# controllerM2.net
KiCad netlist of a schematic drawn in EAGLE
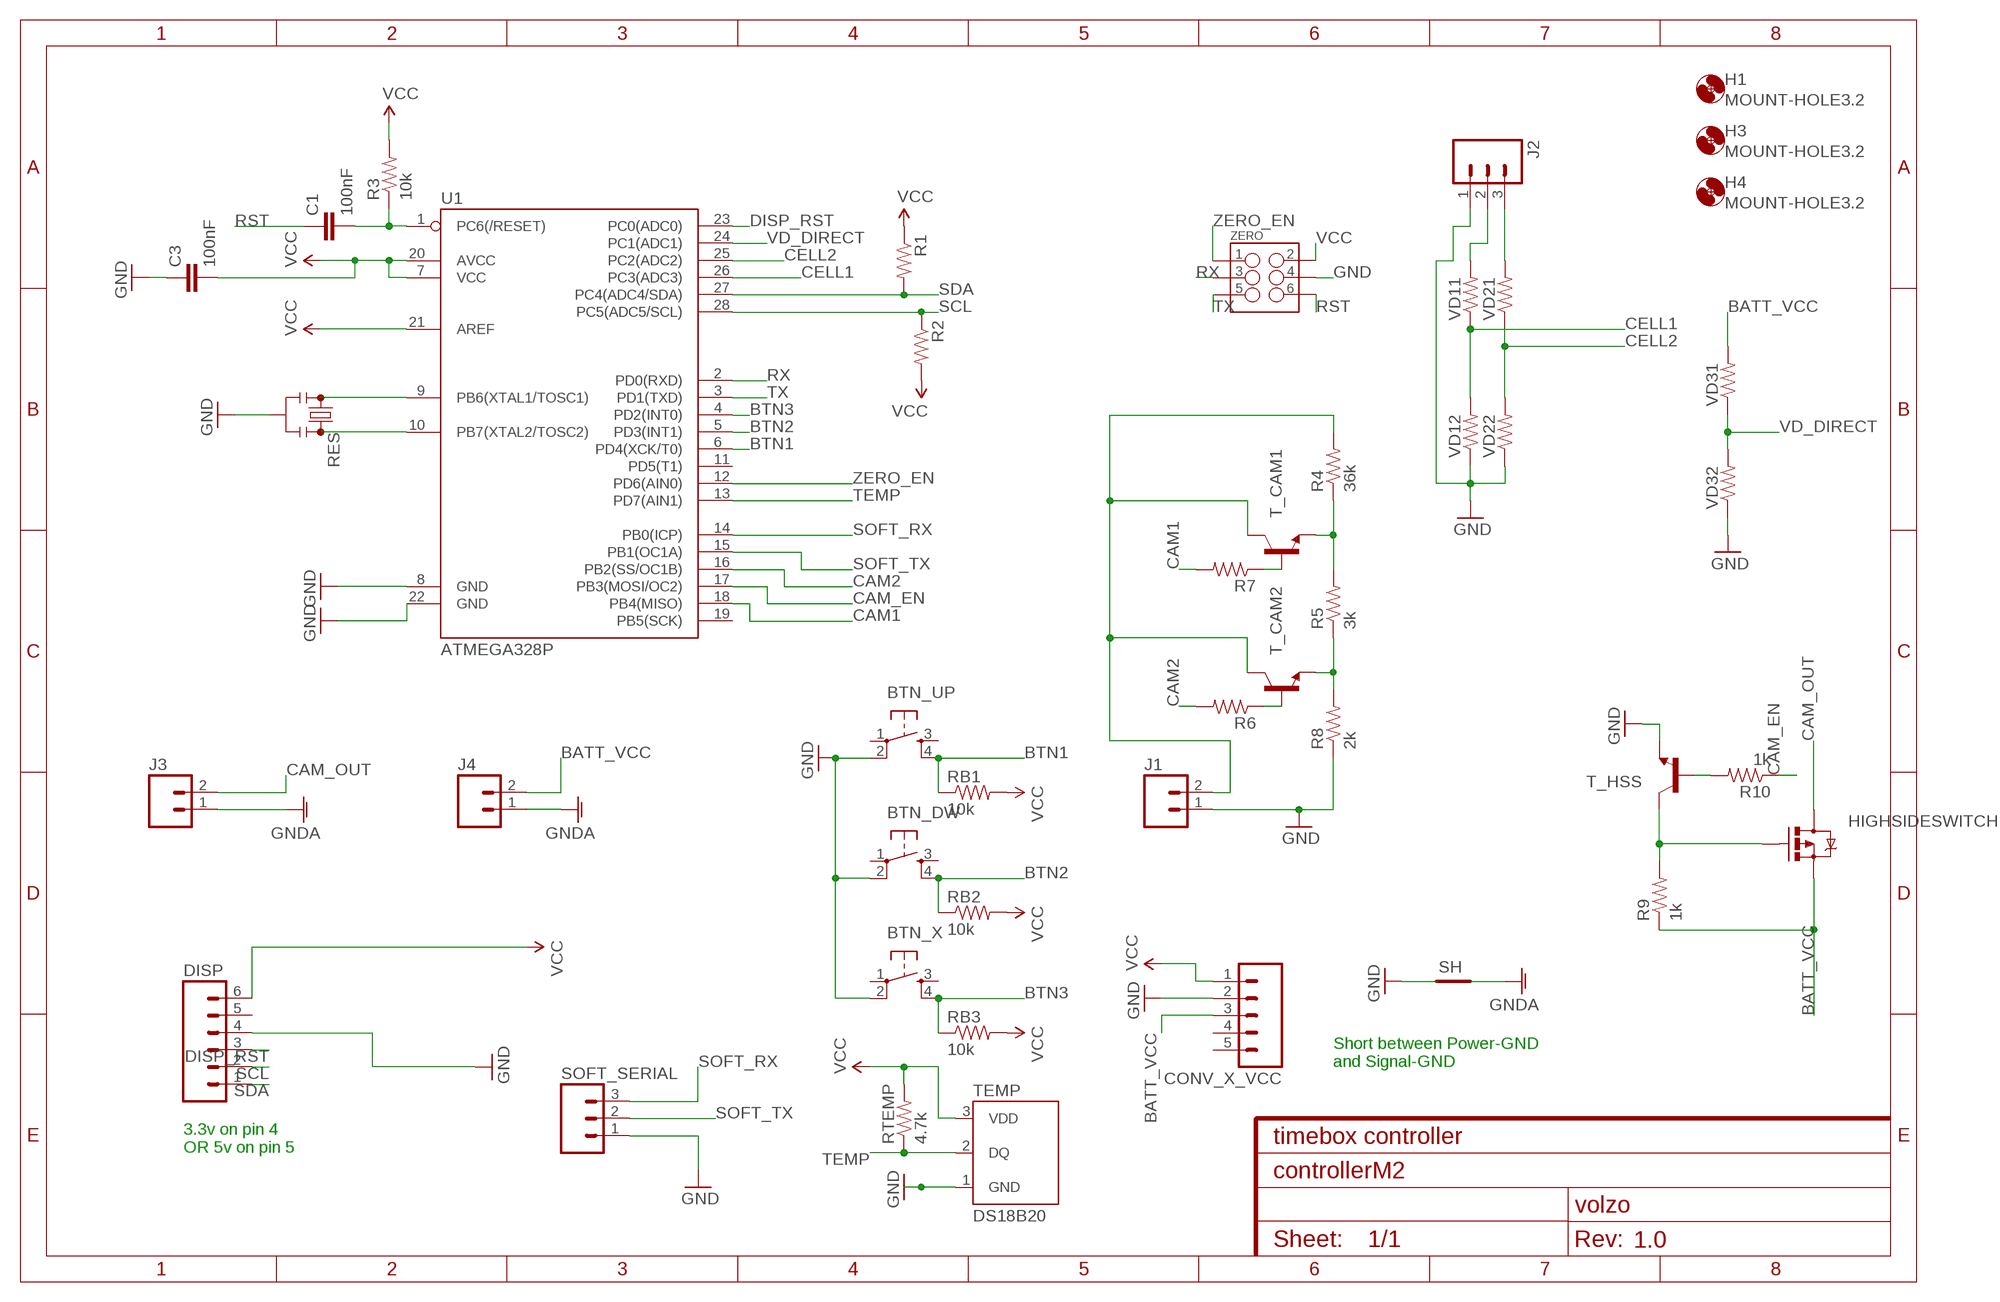
[diagram p0: schematic, sheet 1]

(export (version "E")
  (design (tool "Eeschema 10.0.6"))
  (components
    (comp (ref "BTN_DW")
      (value "TAC_SWITCHPTH")
      (footprint "eagle-import:TACTILE-PTH")
      (libsource (lib "eagle-import") (part "TAC_SWITCHPTH"))
    )
    (comp (ref "BTN_UP")
      (value "TAC_SWITCHPTH")
      (footprint "eagle-import:TACTILE-PTH")
      (libsource (lib "eagle-import") (part "TAC_SWITCHPTH"))
    )
    (comp (ref "BTN_X")
      (value "TAC_SWITCHPTH")
      (footprint "eagle-import:TACTILE-PTH")
      (libsource (lib "eagle-import") (part "TAC_SWITCHPTH"))
    )
    (comp (ref "C1")
      (value "100nF")
      (footprint "eagle-import:CAP-PTH-SMALL")
      (libsource (lib "eagle-import") (part "CAPPTH"))
    )
    (comp (ref "C3")
      (value "100nF")
      (footprint "eagle-import:CAP-PTH-SMALL")
      (libsource (lib "eagle-import") (part "CAPPTH"))
    )
    (comp (ref "CONV_X_VCC")
      (value "M05LOCK")
      (footprint "eagle-import:1X05_LOCK")
      (libsource (lib "eagle-import") (part "M05LOCK"))
    )
    (comp (ref "DISP")
      (value "M06FEMALE_LOCK")
      (footprint "eagle-import:1X06_FEMALE_LOCK.010")
      (libsource (lib "eagle-import") (part "M06FEMALE_LOCK"))
    )
    (comp (ref "H1")
      (value "MOUNT-HOLE3.2")
      (footprint "eagle-import:3,2")
      (libsource (lib "eagle-import") (part "MOUNT-HOLE3.2"))
    )
    (comp (ref "H3")
      (value "MOUNT-HOLE3.2")
      (footprint "eagle-import:3,2")
      (libsource (lib "eagle-import") (part "MOUNT-HOLE3.2"))
    )
    (comp (ref "H4")
      (value "MOUNT-HOLE3.2")
      (footprint "eagle-import:3,2")
      (libsource (lib "eagle-import") (part "MOUNT-HOLE3.2"))
    )
    (comp (ref "HIGHSIDESWITCH")
      (value "MOSFET-PCHANNELNDP6020P_20V_24A_LOW_VGS_TH")
      (footprint "eagle-import:TO220V")
      (libsource (lib "eagle-import") (part "MOSFET-PCHANNELNDP6020P_20V_24A_LOW_VGS_TH"))
    )
    (comp (ref "J1")
      (value "M02LOCK")
      (footprint "eagle-import:1X02_LOCK")
      (libsource (lib "eagle-import") (part "M02LOCK"))
    )
    (comp (ref "J2")
      (value "M03LOCK")
      (footprint "eagle-import:1X03_LOCK")
      (libsource (lib "eagle-import") (part "M03LOCK"))
    )
    (comp (ref "J3")
      (value "M023.5MM_LOCK")
      (footprint "eagle-import:SCREWTERMINAL-3.5MM-2_LOCK")
      (libsource (lib "eagle-import") (part "M023.5MM_LOCK"))
    )
    (comp (ref "J4")
      (value "M023.5MM_LOCK")
      (footprint "eagle-import:SCREWTERMINAL-3.5MM-2_LOCK")
      (libsource (lib "eagle-import") (part "M023.5MM_LOCK"))
    )
    (comp (ref "R1")
      (value "RESISTORAXIAL-0.3")
      (footprint "eagle-import:AXIAL-0.3")
      (libsource (lib "eagle-import") (part "RESISTORAXIAL-0.3"))
    )
    (comp (ref "R2")
      (value "RESISTORAXIAL-0.3")
      (footprint "eagle-import:AXIAL-0.3")
      (libsource (lib "eagle-import") (part "RESISTORAXIAL-0.3"))
    )
    (comp (ref "R3")
      (value "10k")
      (footprint "eagle-import:AXIAL-0.3")
      (libsource (lib "eagle-import") (part "RESISTORAXIAL-0.3"))
    )
    (comp (ref "R4")
      (value "36k")
      (footprint "eagle-import:AXIAL-0.3")
      (libsource (lib "eagle-import") (part "RESISTORAXIAL-0.3"))
    )
    (comp (ref "R5")
      (value "3k")
      (footprint "eagle-import:AXIAL-0.3")
      (libsource (lib "eagle-import") (part "RESISTORAXIAL-0.3"))
    )
    (comp (ref "R6")
      (value "RESISTORAXIAL-0.3")
      (footprint "eagle-import:AXIAL-0.3")
      (libsource (lib "eagle-import") (part "RESISTORAXIAL-0.3"))
    )
    (comp (ref "R7")
      (value "RESISTORAXIAL-0.3")
      (footprint "eagle-import:AXIAL-0.3")
      (libsource (lib "eagle-import") (part "RESISTORAXIAL-0.3"))
    )
    (comp (ref "R8")
      (value "2k")
      (footprint "eagle-import:AXIAL-0.3")
      (libsource (lib "eagle-import") (part "RESISTORAXIAL-0.3"))
    )
    (comp (ref "R9")
      (value "1k")
      (footprint "eagle-import:AXIAL-0.3")
      (libsource (lib "eagle-import") (part "RESISTORAXIAL-0.3"))
    )
    (comp (ref "R10")
      (value "1k")
      (footprint "eagle-import:AXIAL-0.3")
      (libsource (lib "eagle-import") (part "RESISTORAXIAL-0.3"))
    )
    (comp (ref "RB1")
      (value "10k")
      (footprint "eagle-import:AXIAL-0.3")
      (libsource (lib "eagle-import") (part "RESISTORAXIAL-0.3"))
    )
    (comp (ref "RB2")
      (value "10k")
      (footprint "eagle-import:AXIAL-0.3")
      (libsource (lib "eagle-import") (part "RESISTORAXIAL-0.3"))
    )
    (comp (ref "RB3")
      (value "10k")
      (footprint "eagle-import:AXIAL-0.3")
      (libsource (lib "eagle-import") (part "RESISTORAXIAL-0.3"))
    )
    (comp (ref "RES")
      (value "RESONATORPTH")
      (footprint "eagle-import:RESONATOR-PTH")
      (libsource (lib "eagle-import") (part "RESONATORPTH"))
    )
    (comp (ref "RTEMP")
      (value "4.7k")
      (footprint "eagle-import:AXIAL-0.3")
      (libsource (lib "eagle-import") (part "RESISTORAXIAL-0.3"))
    )
    (comp (ref "SH")
      (value "SHORT-HT5")
      (footprint "eagle-import:SHORT_TOP-50")
      (libsource (lib "eagle-import") (part "SHORT-HT5"))
    )
    (comp (ref "SOFT_SERIAL")
      (value "M03LOCK")
      (footprint "eagle-import:1X03_LOCK")
      (libsource (lib "eagle-import") (part "M03LOCK"))
    )
    (comp (ref "TEMP")
      (value "DS18B20")
      (footprint "eagle-import:TO-92-AMMO")
      (libsource (lib "eagle-import") (part "DS18B20"))
    )
    (comp (ref "T_CAM1")
      (value "TRANSISTOR_NPN2N3904")
      (footprint "eagle-import:TO-92")
      (libsource (lib "eagle-import") (part "TRANSISTOR_NPN2N3904"))
    )
    (comp (ref "T_CAM2")
      (value "TRANSISTOR_NPN2N3904")
      (footprint "eagle-import:TO-92")
      (libsource (lib "eagle-import") (part "TRANSISTOR_NPN2N3904"))
    )
    (comp (ref "T_HSS")
      (value "TRANSISTOR_NPN2N3904")
      (footprint "eagle-import:TO-92")
      (libsource (lib "eagle-import") (part "TRANSISTOR_NPN2N3904"))
    )
    (comp (ref "U1")
      (value "ATMEGA328P")
      (footprint "eagle-import:DIL28-3")
      (libsource (lib "eagle-import") (part "ATMEGA328P_PDIP"))
    )
    (comp (ref "VD11")
      (value "RESISTORAXIAL-0.3")
      (footprint "eagle-import:AXIAL-0.3")
      (libsource (lib "eagle-import") (part "RESISTORAXIAL-0.3"))
    )
    (comp (ref "VD12")
      (value "RESISTORAXIAL-0.3")
      (footprint "eagle-import:AXIAL-0.3")
      (libsource (lib "eagle-import") (part "RESISTORAXIAL-0.3"))
    )
    (comp (ref "VD21")
      (value "RESISTORAXIAL-0.3")
      (footprint "eagle-import:AXIAL-0.3")
      (libsource (lib "eagle-import") (part "RESISTORAXIAL-0.3"))
    )
    (comp (ref "VD22")
      (value "RESISTORAXIAL-0.3")
      (footprint "eagle-import:AXIAL-0.3")
      (libsource (lib "eagle-import") (part "RESISTORAXIAL-0.3"))
    )
    (comp (ref "VD31")
      (value "RESISTORAXIAL-0.3")
      (footprint "eagle-import:AXIAL-0.3")
      (libsource (lib "eagle-import") (part "RESISTORAXIAL-0.3"))
    )
    (comp (ref "VD32")
      (value "RESISTORAXIAL-0.3")
      (footprint "eagle-import:AXIAL-0.3")
      (libsource (lib "eagle-import") (part "RESISTORAXIAL-0.3"))
    )
    (comp (ref "ZERO")
      (value "M03X2FEMALE")
      (footprint "eagle-import:2X3")
      (libsource (lib "eagle-import") (part "M03X2FEMALE"))
    )
  )
  (nets
    (net (code "1") (name "/BATT_VCC") (class "Default")
      (node (ref "CONV_X_VCC") (pin "3") (pinfunction "3_3") (pintype "passive"))
      (node (ref "HIGHSIDESWITCH") (pin "3") (pinfunction "S_3") (pintype "passive"))
      (node (ref "J4") (pin "2") (pinfunction "2_2") (pintype "passive"))
      (node (ref "R9") (pin "P$1") (pinfunction "1_P$1") (pintype "passive"))
      (node (ref "VD31") (pin "P$2") (pinfunction "2_P$2") (pintype "passive"))
    )
    (net (code "2") (name "/BTN1") (class "Default")
      (node (ref "BTN_UP") (pin "4") (pinfunction "4_4") (pintype "passive"))
      (node (ref "RB1") (pin "P$1") (pinfunction "1_P$1") (pintype "passive"))
      (node (ref "U1") (pin "6") (pinfunction "PD4(XCK/T0)_6") (pintype "bidirectional"))
    )
    (net (code "3") (name "/BTN2") (class "Default")
      (node (ref "BTN_DW") (pin "4") (pinfunction "4_4") (pintype "passive"))
      (node (ref "RB2") (pin "P$1") (pinfunction "1_P$1") (pintype "passive"))
      (node (ref "U1") (pin "5") (pinfunction "PD3(INT1)_5") (pintype "bidirectional"))
    )
    (net (code "4") (name "/BTN3") (class "Default")
      (node (ref "BTN_X") (pin "4") (pinfunction "4_4") (pintype "passive"))
      (node (ref "RB3") (pin "P$1") (pinfunction "1_P$1") (pintype "passive"))
      (node (ref "U1") (pin "4") (pinfunction "PD2(INT0)_4") (pintype "bidirectional"))
    )
    (net (code "5") (name "/CAM1") (class "Default")
      (node (ref "R7") (pin "P$2") (pinfunction "2_P$2") (pintype "passive"))
      (node (ref "U1") (pin "18") (pinfunction "PB4(MISO)_18") (pintype "bidirectional"))
    )
    (net (code "6") (name "/CAM2") (class "Default")
      (node (ref "R6") (pin "P$2") (pinfunction "2_P$2") (pintype "passive"))
      (node (ref "U1") (pin "16") (pinfunction "PB2(SS/OC1B)_16") (pintype "bidirectional"))
    )
    (net (code "7") (name "/CAM_EN") (class "Default")
      (node (ref "R10") (pin "P$1") (pinfunction "1_P$1") (pintype "passive"))
      (node (ref "U1") (pin "17") (pinfunction "PB3(MOSI/OC2)_17") (pintype "bidirectional"))
    )
    (net (code "8") (name "/CAM_OUT") (class "Default")
      (node (ref "HIGHSIDESWITCH") (pin "2") (pinfunction "D_2") (pintype "passive"))
      (node (ref "J3") (pin "2") (pinfunction "2_2") (pintype "passive"))
    )
    (net (code "9") (name "/CELL1") (class "Default")
      (node (ref "U1") (pin "26") (pinfunction "PC3(ADC3)_26") (pintype "bidirectional"))
      (node (ref "VD11") (pin "P$1") (pinfunction "1_P$1") (pintype "passive"))
      (node (ref "VD12") (pin "P$2") (pinfunction "2_P$2") (pintype "passive"))
    )
    (net (code "10") (name "/CELL2") (class "Default")
      (node (ref "U1") (pin "25") (pinfunction "PC2(ADC2)_25") (pintype "bidirectional"))
      (node (ref "VD21") (pin "P$1") (pinfunction "1_P$1") (pintype "passive"))
      (node (ref "VD22") (pin "P$2") (pinfunction "2_P$2") (pintype "passive"))
    )
    (net (code "11") (name "/DISP_RST") (class "Default")
      (node (ref "DISP") (pin "3") (pinfunction "3_3") (pintype "passive"))
      (node (ref "U1") (pin "23") (pinfunction "PC0(ADC0)_23") (pintype "bidirectional"))
    )
    (net (code "12") (name "/RST") (class "Default")
      (node (ref "C1") (pin "1") (pinfunction "1_1") (pintype "passive"))
      (node (ref "ZERO") (pin "6") (pinfunction "6_6") (pintype "bidirectional"))
    )
    (net (code "13") (name "/RX") (class "Default")
      (node (ref "U1") (pin "2") (pinfunction "PD0(RXD)_2") (pintype "bidirectional"))
      (node (ref "ZERO") (pin "3") (pinfunction "3_3") (pintype "bidirectional"))
    )
    (net (code "14") (name "/SCL") (class "Default")
      (node (ref "DISP") (pin "2") (pinfunction "2_2") (pintype "passive"))
      (node (ref "R2") (pin "P$1") (pinfunction "1_P$1") (pintype "passive"))
      (node (ref "U1") (pin "28") (pinfunction "PC5(ADC5/SCL)_28") (pintype "bidirectional"))
    )
    (net (code "15") (name "/SDA") (class "Default")
      (node (ref "DISP") (pin "1") (pinfunction "1_1") (pintype "passive"))
      (node (ref "R1") (pin "P$2") (pinfunction "2_P$2") (pintype "passive"))
      (node (ref "U1") (pin "27") (pinfunction "PC4(ADC4/SDA)_27") (pintype "bidirectional"))
    )
    (net (code "16") (name "/SOFT_RX") (class "Default")
      (node (ref "SOFT_SERIAL") (pin "3") (pinfunction "3_3") (pintype "passive"))
      (node (ref "U1") (pin "14") (pinfunction "PB0(ICP)_14") (pintype "bidirectional"))
    )
    (net (code "17") (name "/SOFT_TX") (class "Default")
      (node (ref "SOFT_SERIAL") (pin "2") (pinfunction "2_2") (pintype "passive"))
      (node (ref "U1") (pin "15") (pinfunction "PB1(OC1A)_15") (pintype "bidirectional"))
    )
    (net (code "18") (name "/TEMP") (class "Default")
      (node (ref "RTEMP") (pin "P$1") (pinfunction "1_P$1") (pintype "passive"))
      (node (ref "TEMP") (pin "2") (pinfunction "DQ_2") (pintype "bidirectional"))
      (node (ref "U1") (pin "13") (pinfunction "PD7(AIN1)_13") (pintype "bidirectional"))
    )
    (net (code "19") (name "/TX") (class "Default")
      (node (ref "U1") (pin "3") (pinfunction "PD1(TXD)_3") (pintype "bidirectional"))
      (node (ref "ZERO") (pin "5") (pinfunction "5_5") (pintype "bidirectional"))
    )
    (net (code "20") (name "/VD_DIRECT") (class "Default")
      (node (ref "U1") (pin "24") (pinfunction "PC1(ADC1)_24") (pintype "bidirectional"))
      (node (ref "VD31") (pin "P$1") (pinfunction "1_P$1") (pintype "passive"))
      (node (ref "VD32") (pin "P$2") (pinfunction "2_P$2") (pintype "passive"))
    )
    (net (code "21") (name "/ZERO_EN") (class "Default")
      (node (ref "U1") (pin "12") (pinfunction "PD6(AIN0)_12") (pintype "bidirectional"))
      (node (ref "ZERO") (pin "1") (pinfunction "1_1") (pintype "bidirectional"))
    )
    (net (code "22") (name "GND") (class "Default")
      (node (ref "BTN_DW") (pin "2") (pinfunction "2_2") (pintype "passive"))
      (node (ref "BTN_UP") (pin "2") (pinfunction "2_2") (pintype "passive"))
      (node (ref "BTN_X") (pin "2") (pinfunction "2_2") (pintype "passive"))
      (node (ref "C3") (pin "1") (pinfunction "1_1") (pintype "passive"))
      (node (ref "CONV_X_VCC") (pin "2") (pinfunction "2_2") (pintype "passive"))
      (node (ref "DISP") (pin "4") (pinfunction "4_4") (pintype "passive"))
      (node (ref "J1") (pin "1") (pinfunction "1_1") (pintype "passive"))
      (node (ref "J2") (pin "1") (pinfunction "1_1") (pintype "passive"))
      (node (ref "R8") (pin "P$1") (pinfunction "1_P$1") (pintype "passive"))
      (node (ref "RES") (pin "2") (pinfunction "2_2") (pintype "passive"))
      (node (ref "SH") (pin "1") (pinfunction "P$1_1") (pintype "bidirectional"))
      (node (ref "SOFT_SERIAL") (pin "1") (pinfunction "1_1") (pintype "passive"))
      (node (ref "TEMP") (pin "1") (pinfunction "GND_1") (pintype "power_in"))
      (node (ref "T_HSS") (pin "1") (pinfunction "E_1") (pintype "passive"))
      (node (ref "U1") (pin "22") (pinfunction "GND_22") (pintype "bidirectional"))
      (node (ref "U1") (pin "8") (pinfunction "GND_8") (pintype "bidirectional"))
      (node (ref "VD12") (pin "P$1") (pinfunction "1_P$1") (pintype "passive"))
      (node (ref "VD22") (pin "P$1") (pinfunction "1_P$1") (pintype "passive"))
      (node (ref "VD32") (pin "P$1") (pinfunction "1_P$1") (pintype "passive"))
      (node (ref "ZERO") (pin "4") (pinfunction "4_4") (pintype "bidirectional"))
    )
    (net (code "23") (name "GNDA") (class "Default")
      (node (ref "J3") (pin "1") (pinfunction "1_1") (pintype "passive"))
      (node (ref "J4") (pin "1") (pinfunction "1_1") (pintype "passive"))
      (node (ref "SH") (pin "2") (pinfunction "P$2_2") (pintype "bidirectional"))
    )
    (net (code "24") (name "Net-(HIGHSIDESWITCH-G)") (class "Default")
      (node (ref "HIGHSIDESWITCH") (pin "1") (pinfunction "G_1") (pintype "passive"))
      (node (ref "R9") (pin "P$2") (pinfunction "2_P$2") (pintype "passive"))
      (node (ref "T_HSS") (pin "3") (pinfunction "C_3") (pintype "passive"))
    )
    (net (code "25") (name "Net-(R3-1)") (class "Default")
      (node (ref "C1") (pin "2") (pinfunction "2_2") (pintype "passive"))
      (node (ref "R3") (pin "P$1") (pinfunction "1_P$1") (pintype "passive"))
      (node (ref "U1") (pin "1") (pinfunction "PC6(/RESET)_1") (pintype "bidirectional"))
    )
    (net (code "26") (name "Net-(R4-1)") (class "Default")
      (node (ref "R4") (pin "P$1") (pinfunction "1_P$1") (pintype "passive"))
      (node (ref "R5") (pin "P$2") (pinfunction "2_P$2") (pintype "passive"))
      (node (ref "T_CAM1") (pin "1") (pinfunction "E_1") (pintype "passive"))
    )
    (net (code "27") (name "Net-(R4-2)") (class "Default")
      (node (ref "J1") (pin "2") (pinfunction "2_2") (pintype "passive"))
      (node (ref "R4") (pin "P$2") (pinfunction "2_P$2") (pintype "passive"))
      (node (ref "T_CAM1") (pin "3") (pinfunction "C_3") (pintype "passive"))
      (node (ref "T_CAM2") (pin "3") (pinfunction "C_3") (pintype "passive"))
    )
    (net (code "28") (name "Net-(R5-1)") (class "Default")
      (node (ref "R5") (pin "P$1") (pinfunction "1_P$1") (pintype "passive"))
      (node (ref "R8") (pin "P$2") (pinfunction "2_P$2") (pintype "passive"))
      (node (ref "T_CAM2") (pin "1") (pinfunction "E_1") (pintype "passive"))
    )
    (net (code "29") (name "Net-(R6-1)") (class "Default")
      (node (ref "R6") (pin "P$1") (pinfunction "1_P$1") (pintype "passive"))
      (node (ref "T_CAM2") (pin "2") (pinfunction "B_2") (pintype "passive"))
    )
    (net (code "30") (name "Net-(R7-1)") (class "Default")
      (node (ref "R7") (pin "P$1") (pinfunction "1_P$1") (pintype "passive"))
      (node (ref "T_CAM1") (pin "2") (pinfunction "B_2") (pintype "passive"))
    )
    (net (code "31") (name "Net-(R10-2)") (class "Default")
      (node (ref "R10") (pin "P$2") (pinfunction "2_P$2") (pintype "passive"))
      (node (ref "T_HSS") (pin "2") (pinfunction "B_2") (pintype "passive"))
    )
    (net (code "32") (name "Net-(U1-PB6(XTAL1{slash}TOSC1))") (class "Default")
      (node (ref "RES") (pin "1") (pinfunction "1_1") (pintype "passive"))
      (node (ref "U1") (pin "9") (pinfunction "PB6(XTAL1/TOSC1)_9") (pintype "bidirectional"))
    )
    (net (code "33") (name "Net-(U1-PB7(XTAL2{slash}TOSC2))") (class "Default")
      (node (ref "RES") (pin "3") (pinfunction "3_3") (pintype "passive"))
      (node (ref "U1") (pin "10") (pinfunction "PB7(XTAL2/TOSC2)_10") (pintype "bidirectional"))
    )
    (net (code "34") (name "Net-(VD11-2)") (class "Default")
      (node (ref "J2") (pin "2") (pinfunction "2_2") (pintype "passive"))
      (node (ref "VD11") (pin "P$2") (pinfunction "2_P$2") (pintype "passive"))
    )
    (net (code "35") (name "Net-(VD21-2)") (class "Default")
      (node (ref "J2") (pin "3") (pinfunction "3_3") (pintype "passive"))
      (node (ref "VD21") (pin "P$2") (pinfunction "2_P$2") (pintype "passive"))
    )
    (net (code "36") (name "VCC") (class "Default")
      (node (ref "C3") (pin "2") (pinfunction "2_2") (pintype "passive"))
      (node (ref "CONV_X_VCC") (pin "1") (pinfunction "1_1") (pintype "passive"))
      (node (ref "DISP") (pin "6") (pinfunction "6_6") (pintype "passive"))
      (node (ref "R1") (pin "P$1") (pinfunction "1_P$1") (pintype "passive"))
      (node (ref "R2") (pin "P$2") (pinfunction "2_P$2") (pintype "passive"))
      (node (ref "R3") (pin "P$2") (pinfunction "2_P$2") (pintype "passive"))
      (node (ref "RB1") (pin "P$2") (pinfunction "2_P$2") (pintype "passive"))
      (node (ref "RB2") (pin "P$2") (pinfunction "2_P$2") (pintype "passive"))
      (node (ref "RB3") (pin "P$2") (pinfunction "2_P$2") (pintype "passive"))
      (node (ref "RTEMP") (pin "P$2") (pinfunction "2_P$2") (pintype "passive"))
      (node (ref "TEMP") (pin "3") (pinfunction "VDD_3") (pintype "power_in"))
      (node (ref "U1") (pin "20") (pinfunction "AVCC_20") (pintype "bidirectional"))
      (node (ref "U1") (pin "21") (pinfunction "AREF_21") (pintype "bidirectional"))
      (node (ref "U1") (pin "7") (pinfunction "VCC_7") (pintype "bidirectional"))
      (node (ref "ZERO") (pin "2") (pinfunction "2_2") (pintype "bidirectional"))
    )
    (net (code "37") (name "unconnected-(BTN_DW-Pad1)") (class "Default")
      (node (ref "BTN_DW") (pin "1") (pinfunction "1_1") (pintype "passive"))
    )
    (net (code "38") (name "unconnected-(BTN_DW-Pad3)") (class "Default")
      (node (ref "BTN_DW") (pin "3") (pinfunction "3_3") (pintype "passive"))
    )
    (net (code "39") (name "unconnected-(BTN_UP-Pad1)") (class "Default")
      (node (ref "BTN_UP") (pin "1") (pinfunction "1_1") (pintype "passive"))
    )
    (net (code "40") (name "unconnected-(BTN_UP-Pad3)") (class "Default")
      (node (ref "BTN_UP") (pin "3") (pinfunction "3_3") (pintype "passive"))
    )
    (net (code "41") (name "unconnected-(BTN_X-Pad1)") (class "Default")
      (node (ref "BTN_X") (pin "1") (pinfunction "1_1") (pintype "passive"))
    )
    (net (code "42") (name "unconnected-(BTN_X-Pad3)") (class "Default")
      (node (ref "BTN_X") (pin "3") (pinfunction "3_3") (pintype "passive"))
    )
    (net (code "43") (name "unconnected-(CONV_X_VCC-Pad4)") (class "Default")
      (node (ref "CONV_X_VCC") (pin "4") (pinfunction "4_4") (pintype "passive"))
    )
    (net (code "44") (name "unconnected-(CONV_X_VCC-Pad5)") (class "Default")
      (node (ref "CONV_X_VCC") (pin "5") (pinfunction "5_5") (pintype "passive"))
    )
    (net (code "45") (name "unconnected-(DISP-Pad5)") (class "Default")
      (node (ref "DISP") (pin "5") (pinfunction "5_5") (pintype "passive"))
    )
    (net (code "46") (name "unconnected-(U1-PB5(SCK)-Pad19)") (class "Default")
      (node (ref "U1") (pin "19") (pinfunction "PB5(SCK)_19") (pintype "bidirectional"))
    )
    (net (code "47") (name "unconnected-(U1-PD5(T1)-Pad11)") (class "Default")
      (node (ref "U1") (pin "11") (pinfunction "PD5(T1)_11") (pintype "bidirectional"))
    )
  )
)
